# E17-15-IMD_LED.net
KiCad netlist of a schematic drawn in Altium Designer
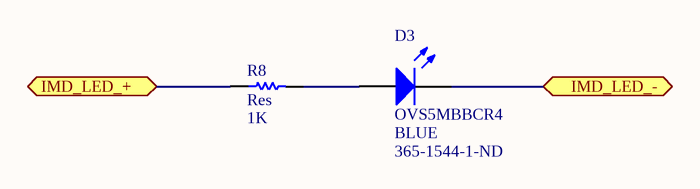
[diagram p0: E17-15-IMD_LED.SchDoc]

(export (version "E")
  (design (tool "Eeschema 10.0.6"))
  (components
    (comp (ref "D3")
      (value "OVS5MBBCR4")
      (footprint "OVS5MBBCR4")
      (description "Typical BLUE LED")
      (fields
        (field (name "COLOUR") "BLUE")
        (field (name "SUPPLIER PART NUMBER 1") "365-1544-1-ND")
        (field (name "PUBLISHER") "Altium Limited")
      )
      (libsource (lib "LEDs") (part "OVS5MBBCR4"))
    )
    (comp (ref "R8")
      (value "Res")
      (footprint "3216[1206]")
      (description "Surface Mount Resistor")
      (fields (field (name "ALTIUM_VALUE") "1K") (field (name "PUBLISHER") "Altium Limited"))
      (libsource (lib "Resistors") (part "Res"))
    )
  )
  (nets
    (net (code "1") (name "/IMD_LED_+") (class "Default")
      (node (ref "R8") (pin "1") (pinfunction "1_1") (pintype "passive"))
    )
    (net (code "2") (name "/IMD_LED_-") (class "Default")
      (node (ref "D3") (pin "2") (pinfunction "K_2") (pintype "passive"))
    )
    (net (code "3") (name "Net-(D3-A)") (class "Default")
      (node (ref "D3") (pin "1") (pinfunction "A_1") (pintype "passive"))
      (node (ref "R8") (pin "2") (pinfunction "2_2") (pintype "passive"))
    )
  )
)
